# MIPI-toBTB-40-pin-AMOLED-HAT.net
KiCad netlist of a schematic drawn in EasyEDA Pro
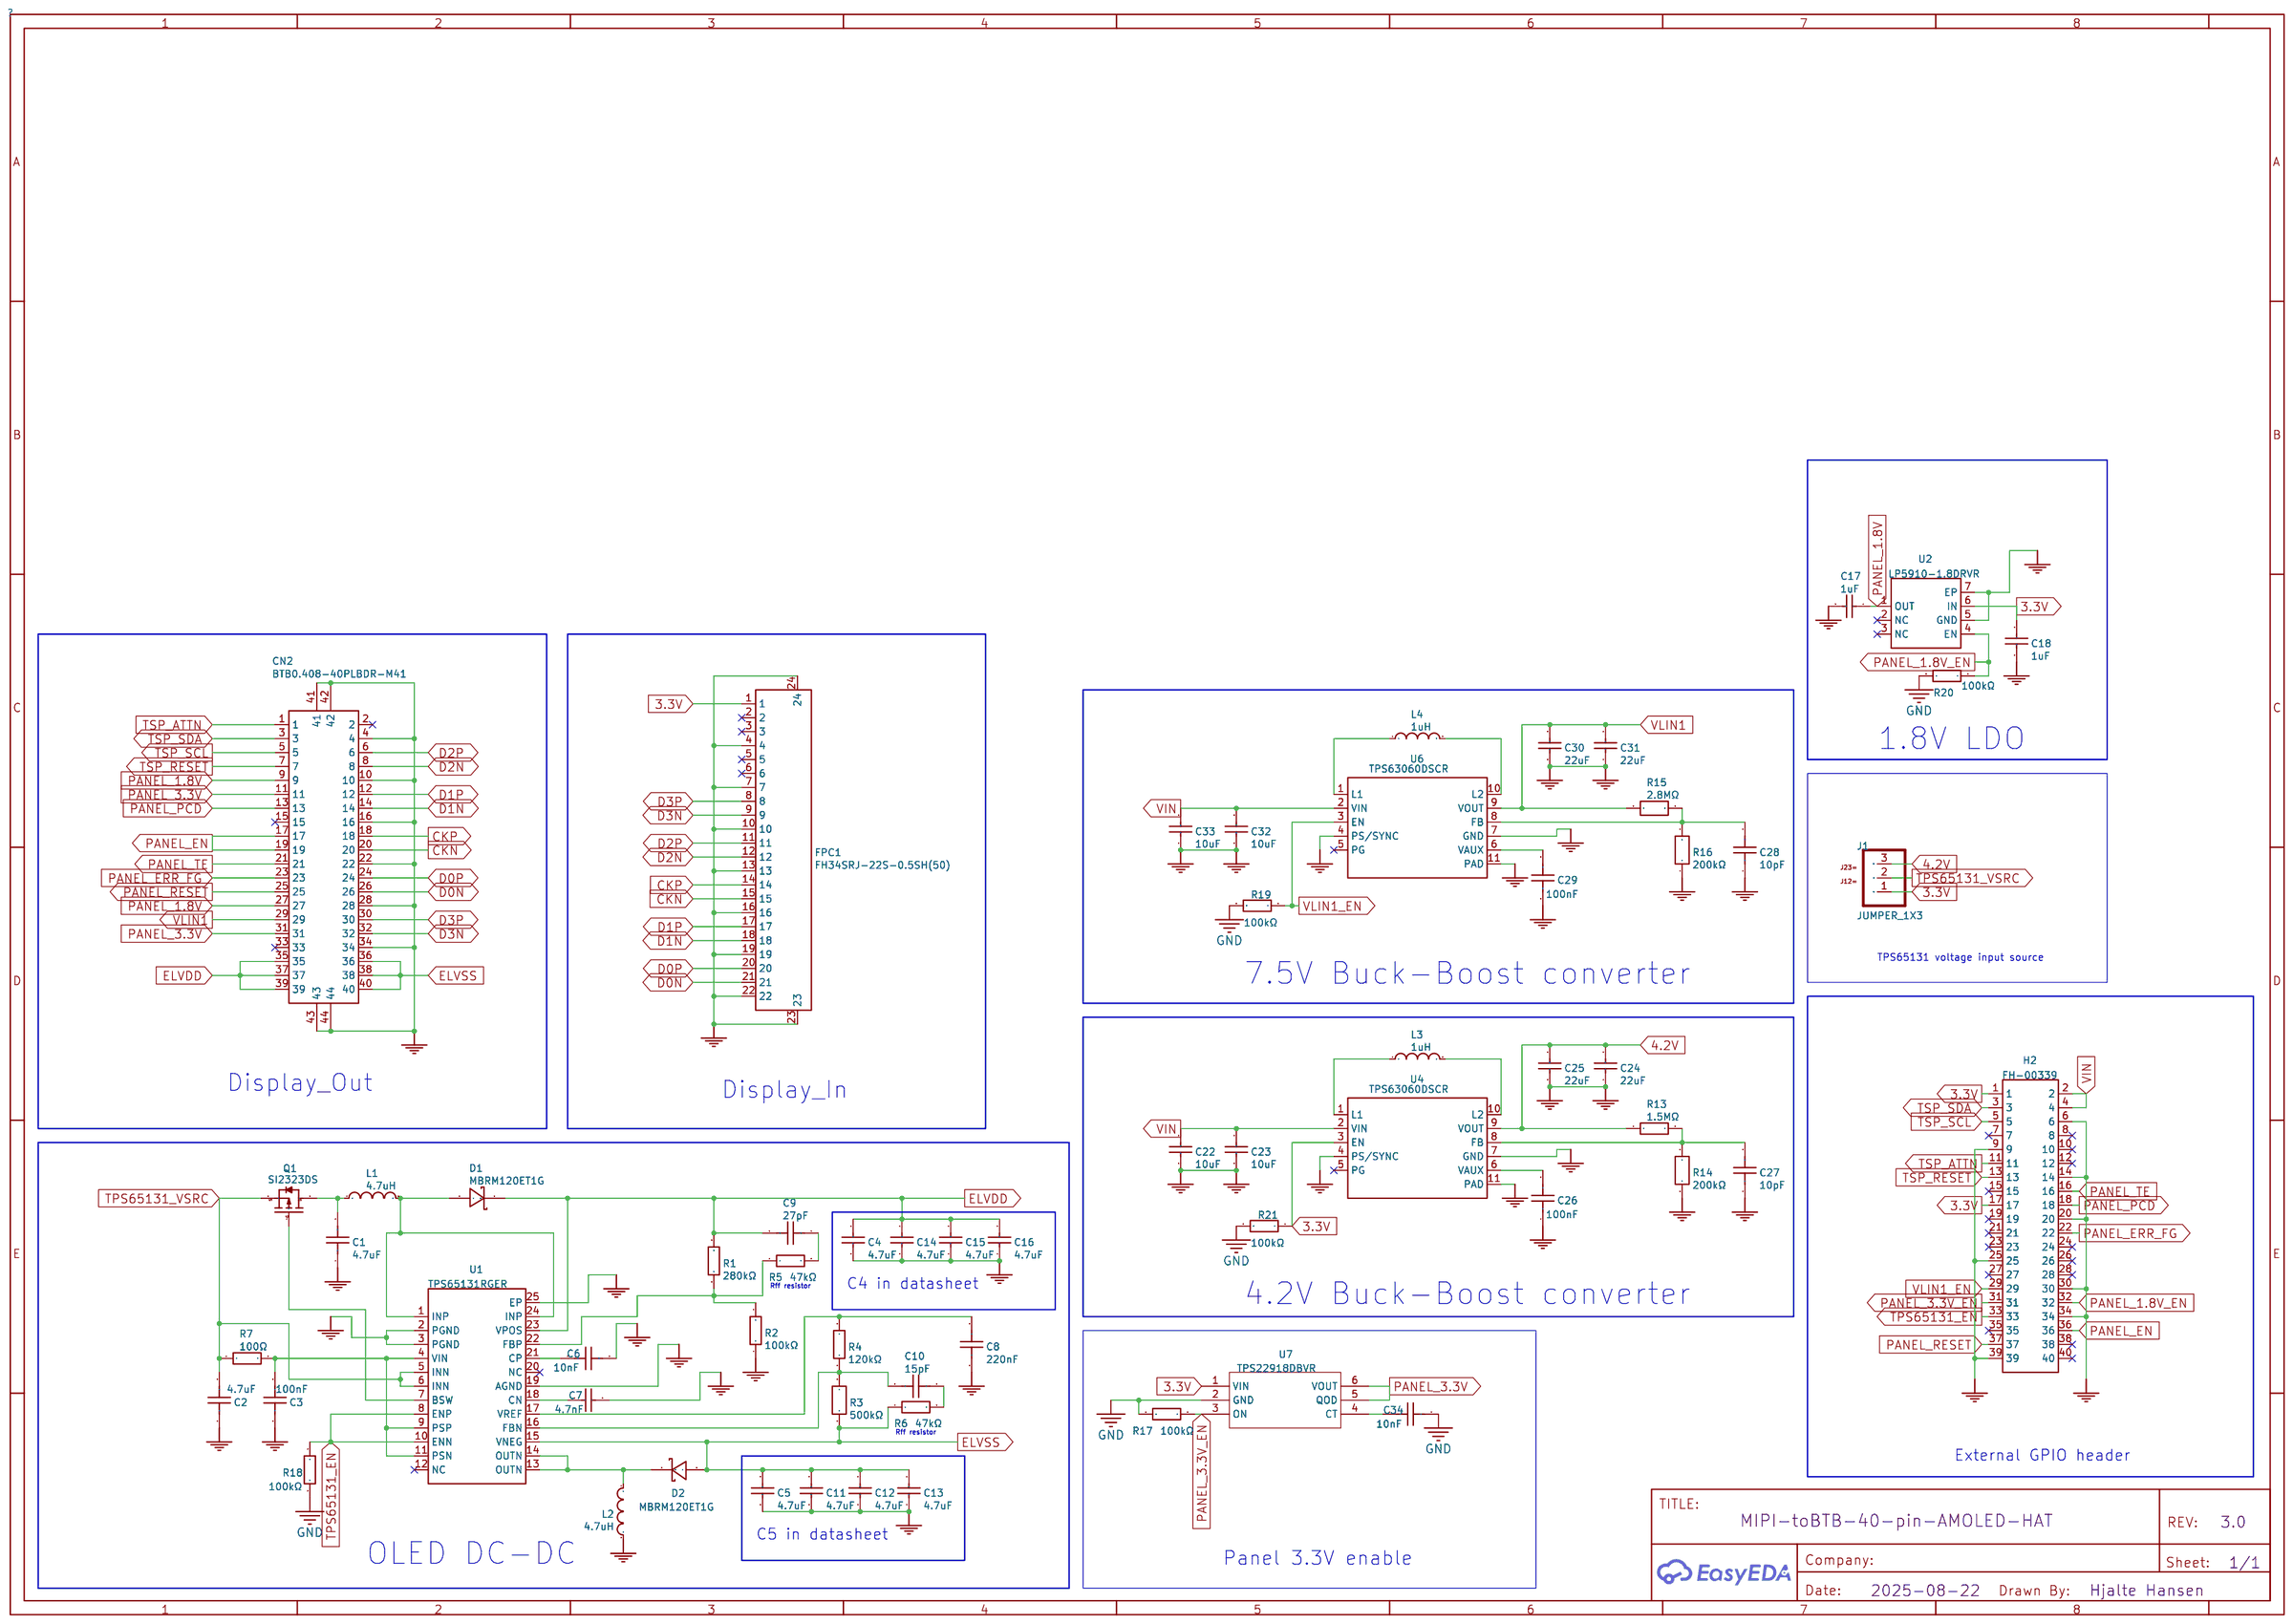
[diagram p0: schematic sheet]

(export (version "E")
  (design (tool "Eeschema 10.0.6"))
  (components
    (comp (ref "C1")
      (value "4.7uF")
      (footprint "easyedapro:C0402")
      (fields
        (field (name "Manufacturer Part") "CL05A475MQ5NRNC")
        (field (name "Manufacturer") "SAMSUNG(三星)")
        (field (name "Contributor") "LCSC")
      )
      (libsource (lib "") (part "4.7uF_1"))
    )
    (comp (ref "C2")
      (value "4.7uF")
      (footprint "easyedapro:C0402")
      (fields
        (field (name "Manufacturer Part") "CL05A475MQ5NRNC")
        (field (name "Manufacturer") "SAMSUNG(三星)")
        (field (name "Contributor") "LCSC")
      )
      (libsource (lib "") (part "4.7uF_1"))
    )
    (comp (ref "C3")
      (value "100nF")
      (footprint "easyedapro:C0402")
      (fields
        (field (name "Manufacturer Part") "CL05B104KP5NNNC")
        (field (name "Manufacturer") "SAMSUNG(三星)")
        (field (name "Contributor") "LCSC")
      )
      (libsource (lib "easyedapro") (part "100nF"))
    )
    (comp (ref "C4")
      (value "4.7uF")
      (footprint "easyedapro:C0805")
      (fields
        (field (name "Manufacturer Part") "CL21A475KAQNNNE")
        (field (name "Manufacturer") "SAMSUNG(三星)")
      )
      (libsource (lib "easyedapro") (part "4.7uF"))
    )
    (comp (ref "C5")
      (value "4.7uF")
      (footprint "easyedapro:C0805")
      (fields
        (field (name "Manufacturer Part") "CL21A475KAQNNNE")
        (field (name "Manufacturer") "SAMSUNG(三星)")
      )
      (libsource (lib "easyedapro") (part "4.7uF"))
    )
    (comp (ref "C6")
      (value "10nF")
      (footprint "easyedapro:C0402")
      (fields
        (field (name "Manufacturer Part") "CL05B103KO5NNNC")
        (field (name "Manufacturer") "SAMSUNG(三星)")
        (field (name "Contributor") "LCSC")
      )
      (libsource (lib "easyedapro") (part "10nF"))
    )
    (comp (ref "C7")
      (value "4.7nF")
      (footprint "easyedapro:C0603")
      (fields
        (field (name "Manufacturer Part") "CL10B472KB8NNNC")
        (field (name "Manufacturer") "SAMSUNG(三星)")
      )
      (libsource (lib "easyedapro") (part "4.7nF"))
    )
    (comp (ref "C8")
      (value "220nF")
      (footprint "easyedapro:C0402")
      (fields
        (field (name "Manufacturer Part") "CL05A224KQ5NNNC")
        (field (name "Manufacturer") "SAMSUNG(三星)")
        (field (name "Contributor") "LCSC")
      )
      (libsource (lib "easyedapro") (part "220nF"))
    )
    (comp (ref "C9")
      (value "27pF")
      (footprint "easyedapro:C0603")
      (fields
        (field (name "Manufacturer Part") "CC0603JRNPO7BN270")
        (field (name "Manufacturer") "YAGEO(国巨)")
        (field (name "Contributor") "lcsc")
      )
      (libsource (lib "easyedapro") (part "27pF"))
    )
    (comp (ref "C10")
      (value "15pF")
      (footprint "easyedapro:C0402")
      (fields
        (field (name "Manufacturer Part") "CC0402KRNPO7BN150")
        (field (name "Manufacturer") "YAGEO(国巨)")
        (field (name "Contributor") "lcsc")
      )
      (libsource (lib "easyedapro") (part "15pF"))
    )
    (comp (ref "C11")
      (value "4.7uF")
      (footprint "easyedapro:C0805")
      (fields
        (field (name "Manufacturer Part") "CL21A475KAQNNNE")
        (field (name "Manufacturer") "SAMSUNG(三星)")
      )
      (libsource (lib "easyedapro") (part "4.7uF"))
    )
    (comp (ref "C12")
      (value "4.7uF")
      (footprint "easyedapro:C0805")
      (fields
        (field (name "Manufacturer Part") "CL21A475KAQNNNE")
        (field (name "Manufacturer") "SAMSUNG(三星)")
      )
      (libsource (lib "easyedapro") (part "4.7uF"))
    )
    (comp (ref "C13")
      (value "4.7uF")
      (footprint "easyedapro:C0805")
      (fields
        (field (name "Manufacturer Part") "CL21A475KAQNNNE")
        (field (name "Manufacturer") "SAMSUNG(三星)")
      )
      (libsource (lib "easyedapro") (part "4.7uF"))
    )
    (comp (ref "C14")
      (value "4.7uF")
      (footprint "easyedapro:C0805")
      (fields
        (field (name "Manufacturer Part") "CL21A475KAQNNNE")
        (field (name "Manufacturer") "SAMSUNG(三星)")
      )
      (libsource (lib "easyedapro") (part "4.7uF"))
    )
    (comp (ref "C15")
      (value "4.7uF")
      (footprint "easyedapro:C0805")
      (fields
        (field (name "Manufacturer Part") "CL21A475KAQNNNE")
        (field (name "Manufacturer") "SAMSUNG(三星)")
      )
      (libsource (lib "easyedapro") (part "4.7uF"))
    )
    (comp (ref "C16")
      (value "4.7uF")
      (footprint "easyedapro:C0805")
      (fields
        (field (name "Manufacturer Part") "CL21A475KAQNNNE")
        (field (name "Manufacturer") "SAMSUNG(三星)")
      )
      (libsource (lib "easyedapro") (part "4.7uF"))
    )
    (comp (ref "C17")
      (value "1uF")
      (footprint "easyedapro:C0603")
      (fields
        (field (name "Manufacturer Part") "CL10A105KO8NNNC")
        (field (name "Manufacturer") "SAMSUNG(三星)")
      )
      (libsource (lib "easyedapro") (part "1uF"))
    )
    (comp (ref "C18")
      (value "1uF")
      (footprint "easyedapro:C0603")
      (fields
        (field (name "Manufacturer Part") "CL10A105KO8NNNC")
        (field (name "Manufacturer") "SAMSUNG(三星)")
      )
      (libsource (lib "") (part "1uF_1"))
    )
    (comp (ref "C22")
      (value "10uF")
      (footprint "easyedapro:C0805")
      (fields
        (field (name "Manufacturer Part") "CL21A106KOQNNNE")
        (field (name "Manufacturer") "SAMSUNG(三星)")
      )
      (libsource (lib "easyedapro") (part "10uF"))
    )
    (comp (ref "C23")
      (value "10uF")
      (footprint "easyedapro:C0805")
      (fields
        (field (name "Manufacturer Part") "CL21A106KOQNNNE")
        (field (name "Manufacturer") "SAMSUNG(三星)")
      )
      (libsource (lib "easyedapro") (part "10uF"))
    )
    (comp (ref "C24")
      (value "22uF")
      (footprint "easyedapro:C0805")
      (fields
        (field (name "Manufacturer Part") "CL21A226MOQNNNE")
        (field (name "Manufacturer") "SAMSUNG(三星)")
      )
      (libsource (lib "easyedapro") (part "22uF"))
    )
    (comp (ref "C25")
      (value "22uF")
      (footprint "easyedapro:C0805")
      (fields
        (field (name "Manufacturer Part") "CL21A226MOQNNNE")
        (field (name "Manufacturer") "SAMSUNG(三星)")
      )
      (libsource (lib "easyedapro") (part "22uF"))
    )
    (comp (ref "C26")
      (value "100nF")
      (footprint "easyedapro:C0402")
      (fields
        (field (name "Manufacturer Part") "CL05B104KP5NNNC")
        (field (name "Manufacturer") "SAMSUNG(三星)")
        (field (name "Contributor") "LCSC")
      )
      (libsource (lib "easyedapro") (part "100nF"))
    )
    (comp (ref "C27")
      (value "10pF")
      (footprint "easyedapro:C0402")
      (fields
        (field (name "Manufacturer Part") "CL05C100JB5NNNC")
        (field (name "Manufacturer") "SAMSUNG(三星)")
      )
      (libsource (lib "easyedapro") (part "10pF"))
    )
    (comp (ref "C28")
      (value "10pF")
      (footprint "easyedapro:C0402")
      (fields
        (field (name "Manufacturer Part") "CL05C100JB5NNNC")
        (field (name "Manufacturer") "SAMSUNG(三星)")
      )
      (libsource (lib "easyedapro") (part "10pF"))
    )
    (comp (ref "C29")
      (value "100nF")
      (footprint "easyedapro:C0402")
      (fields
        (field (name "Manufacturer Part") "CL05B104KP5NNNC")
        (field (name "Manufacturer") "SAMSUNG(三星)")
        (field (name "Contributor") "LCSC")
      )
      (libsource (lib "easyedapro") (part "100nF"))
    )
    (comp (ref "C30")
      (value "22uF")
      (footprint "easyedapro:C0805")
      (fields
        (field (name "Manufacturer Part") "CL21A226MOQNNNE")
        (field (name "Manufacturer") "SAMSUNG(三星)")
      )
      (libsource (lib "easyedapro") (part "22uF"))
    )
    (comp (ref "C31")
      (value "22uF")
      (footprint "easyedapro:C0805")
      (fields
        (field (name "Manufacturer Part") "CL21A226MOQNNNE")
        (field (name "Manufacturer") "SAMSUNG(三星)")
      )
      (libsource (lib "easyedapro") (part "22uF"))
    )
    (comp (ref "C32")
      (value "10uF")
      (footprint "easyedapro:C0805")
      (fields
        (field (name "Manufacturer Part") "CL21A106KOQNNNE")
        (field (name "Manufacturer") "SAMSUNG(三星)")
      )
      (libsource (lib "easyedapro") (part "10uF"))
    )
    (comp (ref "C33")
      (value "10uF")
      (footprint "easyedapro:C0805")
      (fields
        (field (name "Manufacturer Part") "CL21A106KOQNNNE")
        (field (name "Manufacturer") "SAMSUNG(三星)")
      )
      (libsource (lib "easyedapro") (part "10uF"))
    )
    (comp (ref "C34")
      (value "10nF")
      (footprint "easyedapro:C0402")
      (fields
        (field (name "Manufacturer Part") "CL05B103KO5NNNC")
        (field (name "Manufacturer") "SAMSUNG(三星)")
        (field (name "Contributor") "LCSC")
      )
      (libsource (lib "easyedapro") (part "10nF"))
    )
    (comp (ref "CN2")
      (value "BTB0.408-40PLBDR-M41")
      (footprint "easyedapro:CONN-SMD_40P-BTB0.408-40PLBDR-M41")
      (fields (field (name "Manufacturer") "XUNPU(讯普)") (field (name "Contributor") "lcsc"))
      (libsource (lib "easyedapro") (part "BTB0.408-40PLBDR-M41"))
    )
    (comp (ref "D1")
      (value "MBRM120ET1G")
      (footprint "easyedapro:POWERMITE_L2.0-W1.9-LS3.8-RD")
      (fields (field (name "Manufacturer") "onsemi(安森美)") (field (name "Contributor") "LCSC"))
      (libsource (lib "easyedapro") (part "MBRM120ET1G"))
    )
    (comp (ref "D2")
      (value "MBRM120ET1G")
      (footprint "easyedapro:POWERMITE_L2.0-W1.9-LS3.8-RD")
      (fields (field (name "Manufacturer") "onsemi(安森美)") (field (name "Contributor") "LCSC"))
      (libsource (lib "easyedapro") (part "MBRM120ET1G"))
    )
    (comp (ref "FPC1")
      (value "FH34SRJ-22S-0.5SH(50)")
      (footprint "easyedapro:FFC-SMD_22P-P0.50_HRS_FH34SRJ-22S-0.5SH")
      (fields (field (name "Manufacturer") "HRS(广濑)") (field (name "Contributor") "LCSC"))
      (libsource (lib "easyedapro") (part "FH34SRJ-22S-0.5SH(50)"))
    )
    (comp (ref "H2")
      (value "FH-00339")
      (footprint "easyedapro:HDR-SMD_40P-P2.54-V-F-R2-C20-S6.6_FH-00339")
      (fields (field (name "Manufacturer") "Liansheng(连盛)") (field (name "Contributor") "LCSC"))
      (libsource (lib "easyedapro") (part "FH-00339"))
    )
    (comp (ref "J1")
      (value "JUMPER_1X3")
      (footprint "easyedapro:JUMPER_SOLDER")
      (libsource (lib "easyedapro") (part "JUMPER_1X3"))
    )
    (comp (ref "L1")
      (value "4.7uH")
      (footprint "easyedapro:IND-SMD_L4.0-W4.0_FNR40XXS")
      (fields
        (field (name "Manufacturer Part") "FNR4020S4R7MT")
        (field (name "Manufacturer") "cjiang(长江微电)")
        (field (name "Contributor") "LCSC")
      )
      (libsource (lib "easyedapro") (part "4.7uH"))
    )
    (comp (ref "L2")
      (value "4.7uH")
      (footprint "easyedapro:IND-SMD_L4.0-W4.0_FNR40XXS")
      (fields
        (field (name "Manufacturer Part") "FNR4020S4R7MT")
        (field (name "Manufacturer") "cjiang(长江微电)")
        (field (name "Contributor") "LCSC")
      )
      (libsource (lib "") (part "4.7uH_1"))
    )
    (comp (ref "L3")
      (value "1uH")
      (footprint "easyedapro:IND-SMD_L4.5-W4.1_GSSM0420")
      (fields
        (field (name "Manufacturer Part") "MDA4020-1R0M")
        (field (name "Manufacturer") "KOHERelec(科或)")
        (field (name "Contributor") "lcsc")
      )
      (libsource (lib "easyedapro") (part "1uH"))
    )
    (comp (ref "L4")
      (value "1uH")
      (footprint "easyedapro:IND-SMD_L4.5-W4.1_GSSM0420")
      (fields
        (field (name "Manufacturer Part") "MDA4020-1R0M")
        (field (name "Manufacturer") "KOHERelec(科或)")
        (field (name "Contributor") "lcsc")
      )
      (libsource (lib "easyedapro") (part "1uH"))
    )
    (comp (ref "Q1")
      (value "SI2323DS")
      (footprint "easyedapro:SOT-23-3_L2.9-W1.3-P1.90-LS2.4-BR")
      (fields (field (name "Manufacturer") "TECH PUBLIC(台舟)") (field (name "Contributor") "lcsc"))
      (libsource (lib "easyedapro") (part "SI2323DS"))
    )
    (comp (ref "R1")
      (value "280kΩ")
      (footprint "easyedapro:R0603")
      (fields
        (field (name "Manufacturer Part") "0603WAF2803T5E")
        (field (name "Manufacturer") "UNI-ROYAL(厚声)")
      )
      (libsource (lib "easyedapro") (part "280kΩ"))
    )
    (comp (ref "R2")
      (value "100kΩ")
      (footprint "easyedapro:R0603")
      (fields
        (field (name "Manufacturer Part") "0603WAF1003T5E")
        (field (name "Manufacturer") "UNI-ROYAL(厚声)")
      )
      (libsource (lib "easyedapro") (part "100kΩ"))
    )
    (comp (ref "R3")
      (value "500kΩ")
      (footprint "easyedapro:R0603")
      (fields
        (field (name "Manufacturer Part") "AR03BTCX5003N")
        (field (name "Manufacturer") "Viking(光颉)")
        (field (name "Contributor") "LCSC")
      )
      (libsource (lib "easyedapro") (part "500kΩ"))
    )
    (comp (ref "R4")
      (value "120kΩ")
      (footprint "easyedapro:R0603")
      (fields
        (field (name "Manufacturer Part") "0603WAF1203T5E")
        (field (name "Manufacturer") "UNI-ROYAL(厚声)")
      )
      (libsource (lib "easyedapro") (part "120kΩ"))
    )
    (comp (ref "R5")
      (value "47kΩ")
      (footprint "easyedapro:R0603")
      (fields (field (name "Manufacturer Part") "RC0603FR-0747KL") (field (name "Manufacturer") "YAGEO(国巨)"))
      (libsource (lib "easyedapro") (part "47kΩ"))
    )
    (comp (ref "R6")
      (value "47kΩ")
      (footprint "easyedapro:R0603")
      (fields (field (name "Manufacturer Part") "RC0603FR-0747KL") (field (name "Manufacturer") "YAGEO(国巨)"))
      (libsource (lib "easyedapro") (part "47kΩ"))
    )
    (comp (ref "R7")
      (value "100Ω")
      (footprint "easyedapro:R0402")
      (fields (field (name "Manufacturer Part") "RC0402FR-07100RL") (field (name "Manufacturer") "YAGEO(国巨)"))
      (libsource (lib "easyedapro") (part "100Ω"))
    )
    (comp (ref "R13")
      (value "1.5MΩ")
      (footprint "easyedapro:R0603")
      (fields (field (name "Manufacturer Part") "RC0603FR-071M5L") (field (name "Manufacturer") "YAGEO(国巨)"))
      (libsource (lib "easyedapro") (part "1.5MΩ"))
    )
    (comp (ref "R14")
      (value "200kΩ")
      (footprint "easyedapro:R0805")
      (fields
        (field (name "Manufacturer Part") "FRC0805F2003TS")
        (field (name "Manufacturer") "FOJAN(富捷)")
        (field (name "Contributor") "lcsc")
      )
      (libsource (lib "easyedapro") (part "200kΩ"))
    )
    (comp (ref "R15")
      (value "2.8MΩ")
      (footprint "easyedapro:R0603")
      (fields
        (field (name "Manufacturer Part") "RC0603FR-072M8L")
        (field (name "Manufacturer") "YAGEO(国巨)")
        (field (name "Contributor") "LCSC")
      )
      (libsource (lib "easyedapro") (part "2.8MΩ"))
    )
    (comp (ref "R16")
      (value "200kΩ")
      (footprint "easyedapro:R0805")
      (fields
        (field (name "Manufacturer Part") "FRC0805F2003TS")
        (field (name "Manufacturer") "FOJAN(富捷)")
        (field (name "Contributor") "lcsc")
      )
      (libsource (lib "easyedapro") (part "200kΩ"))
    )
    (comp (ref "R17")
      (value "100kΩ")
      (footprint "easyedapro:R0603")
      (fields
        (field (name "Manufacturer Part") "0603WAF1003T5E")
        (field (name "Manufacturer") "UNI-ROYAL(厚声)")
      )
      (libsource (lib "easyedapro") (part "100kΩ"))
    )
    (comp (ref "R18")
      (value "100kΩ")
      (footprint "easyedapro:R0603")
      (fields
        (field (name "Manufacturer Part") "0603WAF1003T5E")
        (field (name "Manufacturer") "UNI-ROYAL(厚声)")
      )
      (libsource (lib "easyedapro") (part "100kΩ"))
    )
    (comp (ref "R19")
      (value "100kΩ")
      (footprint "easyedapro:R0603")
      (fields
        (field (name "Manufacturer Part") "0603WAF1003T5E")
        (field (name "Manufacturer") "UNI-ROYAL(厚声)")
      )
      (libsource (lib "easyedapro") (part "100kΩ"))
    )
    (comp (ref "R20")
      (value "100kΩ")
      (footprint "easyedapro:R0603")
      (fields
        (field (name "Manufacturer Part") "0603WAF1003T5E")
        (field (name "Manufacturer") "UNI-ROYAL(厚声)")
      )
      (libsource (lib "easyedapro") (part "100kΩ"))
    )
    (comp (ref "R21")
      (value "100kΩ")
      (footprint "easyedapro:R0603")
      (fields
        (field (name "Manufacturer Part") "0603WAF1003T5E")
        (field (name "Manufacturer") "UNI-ROYAL(厚声)")
      )
      (libsource (lib "easyedapro") (part "100kΩ"))
    )
    (comp (ref "U1")
      (value "TPS65131RGER")
      (footprint "easyedapro:QFN-24_L4.0-W4.0-P0.50-TL-EP2.6")
      (fields (field (name "Manufacturer") "TI(德州仪器)"))
      (libsource (lib "easyedapro") (part "TPS65131RGER"))
    )
    (comp (ref "U2")
      (value "LP5910-1.8DRVR")
      (footprint "easyedapro:WSON-6_L2.0-W2.0-P0.65-TL-EP")
      (fields (field (name "Manufacturer") "TI(德州仪器)") (field (name "Contributor") "LCSC"))
      (libsource (lib "easyedapro") (part "LP5910-1.8DRVR"))
    )
    (comp (ref "U4")
      (value "TPS63060DSCR")
      (footprint "easyedapro:WSON-10_L3.0-W3.0-P0.50-BL-EP-A")
      (fields (field (name "Manufacturer") "TI(德州仪器)"))
      (libsource (lib "easyedapro") (part "TPS63060DSCR"))
    )
    (comp (ref "U6")
      (value "TPS63060DSCR")
      (footprint "easyedapro:WSON-10_L3.0-W3.0-P0.50-BL-EP-A")
      (fields (field (name "Manufacturer") "TI(德州仪器)"))
      (libsource (lib "easyedapro") (part "TPS63060DSCR"))
    )
    (comp (ref "U7")
      (value "TPS22918DBVR")
      (footprint "easyedapro:SOT-23-6_L2.9-W1.6-P0.95-LS2.8-BR")
      (fields (field (name "Manufacturer") "TI(德州仪器)"))
      (libsource (lib "easyedapro") (part "TPS22918DBVR"))
    )
  )
  (nets
    (net (code "1") (name "3.3V") (class "Default")
      (node (ref "C18") (pin "1") (pinfunction "1_1") (pintype "input"))
      (node (ref "FPC1") (pin "1") (pinfunction "1_1") (pintype "unspecified"))
      (node (ref "H2") (pin "1") (pinfunction "1_1") (pintype "unspecified"))
      (node (ref "H2") (pin "17") (pinfunction "17_17") (pintype "unspecified"))
      (node (ref "J1") (pin "1") (pinfunction "VCC_1") (pintype "unspecified"))
      (node (ref "R21") (pin "1") (pinfunction "1_1") (pintype "input"))
      (node (ref "U2") (pin "6") (pinfunction "IN_6") (pintype "unspecified"))
      (node (ref "U4") (pin "3") (pinfunction "EN_3") (pintype "unspecified"))
      (node (ref "U7") (pin "1") (pinfunction "VIN_1") (pintype "unspecified"))
    )
    (net (code "2") (name "4.2V") (class "Default")
      (node (ref "C24") (pin "2") (pinfunction "2_2") (pintype "input"))
      (node (ref "C25") (pin "2") (pinfunction "2_2") (pintype "input"))
      (node (ref "J1") (pin "3") (pinfunction "GND_3") (pintype "unspecified"))
      (node (ref "R13") (pin "1") (pinfunction "1_1") (pintype "input"))
      (node (ref "U4") (pin "9") (pinfunction "VOUT_9") (pintype "unspecified"))
    )
    (net (code "3") (name "CKN") (class "Default")
      (node (ref "CN2") (pin "20") (pinfunction "20_20") (pintype "unspecified"))
      (node (ref "FPC1") (pin "15") (pinfunction "15_15") (pintype "unspecified"))
    )
    (net (code "4") (name "CKP") (class "Default")
      (node (ref "CN2") (pin "18") (pinfunction "18_18") (pintype "unspecified"))
      (node (ref "FPC1") (pin "14") (pinfunction "14_14") (pintype "unspecified"))
    )
    (net (code "5") (name "D0N") (class "Default")
      (node (ref "CN2") (pin "26") (pinfunction "26_26") (pintype "unspecified"))
      (node (ref "FPC1") (pin "21") (pinfunction "21_21") (pintype "unspecified"))
    )
    (net (code "6") (name "D0P") (class "Default")
      (node (ref "CN2") (pin "24") (pinfunction "24_24") (pintype "unspecified"))
      (node (ref "FPC1") (pin "20") (pinfunction "20_20") (pintype "unspecified"))
    )
    (net (code "7") (name "D1N") (class "Default")
      (node (ref "CN2") (pin "14") (pinfunction "14_14") (pintype "unspecified"))
      (node (ref "FPC1") (pin "18") (pinfunction "18_18") (pintype "unspecified"))
    )
    (net (code "8") (name "D1P") (class "Default")
      (node (ref "CN2") (pin "12") (pinfunction "12_12") (pintype "unspecified"))
      (node (ref "FPC1") (pin "17") (pinfunction "17_17") (pintype "unspecified"))
    )
    (net (code "9") (name "D2N") (class "Default")
      (node (ref "CN2") (pin "8") (pinfunction "8_8") (pintype "unspecified"))
      (node (ref "FPC1") (pin "12") (pinfunction "12_12") (pintype "unspecified"))
    )
    (net (code "10") (name "D2P") (class "Default")
      (node (ref "CN2") (pin "6") (pinfunction "6_6") (pintype "unspecified"))
      (node (ref "FPC1") (pin "11") (pinfunction "11_11") (pintype "unspecified"))
    )
    (net (code "11") (name "D3N") (class "Default")
      (node (ref "CN2") (pin "32") (pinfunction "32_32") (pintype "unspecified"))
      (node (ref "FPC1") (pin "9") (pinfunction "9_9") (pintype "unspecified"))
    )
    (net (code "12") (name "D3P") (class "Default")
      (node (ref "CN2") (pin "30") (pinfunction "30_30") (pintype "unspecified"))
      (node (ref "FPC1") (pin "8") (pinfunction "8_8") (pintype "unspecified"))
    )
    (net (code "13") (name "ELVDD") (class "Default")
      (node (ref "C14") (pin "2") (pinfunction "2_2") (pintype "input"))
      (node (ref "C15") (pin "2") (pinfunction "2_2") (pintype "input"))
      (node (ref "C16") (pin "2") (pinfunction "2_2") (pintype "input"))
      (node (ref "C4") (pin "2") (pinfunction "2_2") (pintype "input"))
      (node (ref "C9") (pin "2") (pinfunction "2_2") (pintype "unspecified"))
      (node (ref "CN2") (pin "35") (pinfunction "35_35") (pintype "unspecified"))
      (node (ref "CN2") (pin "37") (pinfunction "37_37") (pintype "unspecified"))
      (node (ref "CN2") (pin "39") (pinfunction "39_39") (pintype "unspecified"))
      (node (ref "D1") (pin "1") (pinfunction "C_1") (pintype "unspecified"))
      (node (ref "R1") (pin "2") (pinfunction "2_2") (pintype "input"))
      (node (ref "U1") (pin "23") (pinfunction "VPOS_23") (pintype "unspecified"))
    )
    (net (code "14") (name "ELVSS") (class "Default")
      (node (ref "C11") (pin "2") (pinfunction "2_2") (pintype "input"))
      (node (ref "C12") (pin "2") (pinfunction "2_2") (pintype "input"))
      (node (ref "C13") (pin "2") (pinfunction "2_2") (pintype "input"))
      (node (ref "C5") (pin "2") (pinfunction "2_2") (pintype "input"))
      (node (ref "CN2") (pin "36") (pinfunction "36_36") (pintype "unspecified"))
      (node (ref "CN2") (pin "38") (pinfunction "38_38") (pintype "unspecified"))
      (node (ref "CN2") (pin "40") (pinfunction "40_40") (pintype "unspecified"))
      (node (ref "D2") (pin "2") (pinfunction "A_2") (pintype "unspecified"))
      (node (ref "R3") (pin "1") (pinfunction "1_1") (pintype "unspecified"))
      (node (ref "R6") (pin "1") (pinfunction "1_1") (pintype "input"))
      (node (ref "U1") (pin "15") (pinfunction "VNEG_15") (pintype "unspecified"))
    )
    (net (code "15") (name "GND") (class "Default")
      (node (ref "C1") (pin "1") (pinfunction "1_1") (pintype "unspecified"))
      (node (ref "C11") (pin "1") (pinfunction "1_1") (pintype "input"))
      (node (ref "C12") (pin "1") (pinfunction "1_1") (pintype "input"))
      (node (ref "C13") (pin "1") (pinfunction "1_1") (pintype "input"))
      (node (ref "C14") (pin "1") (pinfunction "1_1") (pintype "input"))
      (node (ref "C15") (pin "1") (pinfunction "1_1") (pintype "input"))
      (node (ref "C16") (pin "1") (pinfunction "1_1") (pintype "input"))
      (node (ref "C17") (pin "2") (pinfunction "2_2") (pintype "input"))
      (node (ref "C18") (pin "2") (pinfunction "2_2") (pintype "input"))
      (node (ref "C2") (pin "1") (pinfunction "1_1") (pintype "unspecified"))
      (node (ref "C22") (pin "1") (pinfunction "1_1") (pintype "input"))
      (node (ref "C23") (pin "1") (pinfunction "1_1") (pintype "input"))
      (node (ref "C24") (pin "1") (pinfunction "1_1") (pintype "input"))
      (node (ref "C25") (pin "1") (pinfunction "1_1") (pintype "input"))
      (node (ref "C26") (pin "1") (pinfunction "1_1") (pintype "unspecified"))
      (node (ref "C27") (pin "1") (pinfunction "1_1") (pintype "unspecified"))
      (node (ref "C28") (pin "1") (pinfunction "1_1") (pintype "unspecified"))
      (node (ref "C29") (pin "1") (pinfunction "1_1") (pintype "unspecified"))
      (node (ref "C3") (pin "1") (pinfunction "1_1") (pintype "unspecified"))
      (node (ref "C30") (pin "1") (pinfunction "1_1") (pintype "input"))
      (node (ref "C31") (pin "1") (pinfunction "1_1") (pintype "input"))
      (node (ref "C32") (pin "1") (pinfunction "1_1") (pintype "input"))
      (node (ref "C33") (pin "1") (pinfunction "1_1") (pintype "input"))
      (node (ref "C34") (pin "2") (pinfunction "2_2") (pintype "unspecified"))
      (node (ref "C4") (pin "1") (pinfunction "1_1") (pintype "input"))
      (node (ref "C5") (pin "1") (pinfunction "1_1") (pintype "input"))
      (node (ref "C6") (pin "2") (pinfunction "2_2") (pintype "unspecified"))
      (node (ref "C7") (pin "2") (pinfunction "2_2") (pintype "input"))
      (node (ref "C8") (pin "1") (pinfunction "1_1") (pintype "unspecified"))
      (node (ref "CN2") (pin "10") (pinfunction "10_10") (pintype "unspecified"))
      (node (ref "CN2") (pin "16") (pinfunction "16_16") (pintype "unspecified"))
      (node (ref "CN2") (pin "22") (pinfunction "22_22") (pintype "unspecified"))
      (node (ref "CN2") (pin "28") (pinfunction "28_28") (pintype "unspecified"))
      (node (ref "CN2") (pin "34") (pinfunction "34_34") (pintype "unspecified"))
      (node (ref "CN2") (pin "4") (pinfunction "4_4") (pintype "unspecified"))
      (node (ref "CN2") (pin "41") (pinfunction "41_41") (pintype "unspecified"))
      (node (ref "CN2") (pin "42") (pinfunction "42_42") (pintype "unspecified"))
      (node (ref "CN2") (pin "43") (pinfunction "43_43") (pintype "unspecified"))
      (node (ref "CN2") (pin "44") (pinfunction "44_44") (pintype "unspecified"))
      (node (ref "FPC1") (pin "10") (pinfunction "10_10") (pintype "unspecified"))
      (node (ref "FPC1") (pin "13") (pinfunction "13_13") (pintype "unspecified"))
      (node (ref "FPC1") (pin "16") (pinfunction "16_16") (pintype "unspecified"))
      (node (ref "FPC1") (pin "19") (pinfunction "19_19") (pintype "unspecified"))
      (node (ref "FPC1") (pin "22") (pinfunction "22_22") (pintype "unspecified"))
      (node (ref "FPC1") (pin "23") (pinfunction "23_23") (pintype "unspecified"))
      (node (ref "FPC1") (pin "24") (pinfunction "24_24") (pintype "unspecified"))
      (node (ref "FPC1") (pin "4") (pinfunction "4_4") (pintype "unspecified"))
      (node (ref "FPC1") (pin "7") (pinfunction "7_7") (pintype "unspecified"))
      (node (ref "H2") (pin "14") (pinfunction "14_14") (pintype "unspecified"))
      (node (ref "H2") (pin "20") (pinfunction "20_20") (pintype "unspecified"))
      (node (ref "H2") (pin "25") (pinfunction "25_25") (pintype "unspecified"))
      (node (ref "H2") (pin "30") (pinfunction "30_30") (pintype "unspecified"))
      (node (ref "H2") (pin "34") (pinfunction "34_34") (pintype "unspecified"))
      (node (ref "H2") (pin "39") (pinfunction "39_39") (pintype "unspecified"))
      (node (ref "H2") (pin "6") (pinfunction "6_6") (pintype "unspecified"))
      (node (ref "H2") (pin "9") (pinfunction "9_9") (pintype "unspecified"))
      (node (ref "L2") (pin "2") (pinfunction "2_2") (pintype "unspecified"))
      (node (ref "R14") (pin "1") (pinfunction "1_1") (pintype "unspecified"))
      (node (ref "R16") (pin "1") (pinfunction "1_1") (pintype "unspecified"))
      (node (ref "R17") (pin "2") (pinfunction "2_2") (pintype "input"))
      (node (ref "R18") (pin "2") (pinfunction "2_2") (pintype "input"))
      (node (ref "R19") (pin "2") (pinfunction "2_2") (pintype "input"))
      (node (ref "R2") (pin "1") (pinfunction "1_1") (pintype "input"))
      (node (ref "R20") (pin "2") (pinfunction "2_2") (pintype "input"))
      (node (ref "R21") (pin "2") (pinfunction "2_2") (pintype "input"))
      (node (ref "U1") (pin "19") (pinfunction "AGND_19") (pintype "unspecified"))
      (node (ref "U1") (pin "2") (pinfunction "PGND_2") (pintype "unspecified"))
      (node (ref "U1") (pin "25") (pinfunction "EP_25") (pintype "unspecified"))
      (node (ref "U1") (pin "3") (pinfunction "PGND_3") (pintype "unspecified"))
      (node (ref "U2") (pin "5") (pinfunction "GND_5") (pintype "unspecified"))
      (node (ref "U2") (pin "7") (pinfunction "EP_7") (pintype "unspecified"))
      (node (ref "U4") (pin "11") (pinfunction "PAD_11") (pintype "unspecified"))
      (node (ref "U4") (pin "4") (pinfunction "PS/SYNC_4") (pintype "unspecified"))
      (node (ref "U4") (pin "7") (pinfunction "GND_7") (pintype "unspecified"))
      (node (ref "U6") (pin "11") (pinfunction "PAD_11") (pintype "unspecified"))
      (node (ref "U6") (pin "4") (pinfunction "PS/SYNC_4") (pintype "unspecified"))
      (node (ref "U6") (pin "7") (pinfunction "GND_7") (pintype "unspecified"))
      (node (ref "U7") (pin "2") (pinfunction "GND_2") (pintype "unspecified"))
    )
    (net (code "16") (name "Net-(C9-Pad1)") (class "Default")
      (node (ref "C9") (pin "1") (pinfunction "1_1") (pintype "unspecified"))
      (node (ref "R5") (pin "2") (pinfunction "2_2") (pintype "input"))
    )
    (net (code "17") (name "Net-(C10-Pad1)") (class "Default")
      (node (ref "C10") (pin "1") (pinfunction "1_1") (pintype "unspecified"))
      (node (ref "R6") (pin "2") (pinfunction "2_2") (pintype "input"))
    )
    (net (code "18") (name "Net-(D1-A)") (class "Default")
      (node (ref "D1") (pin "2") (pinfunction "A_2") (pintype "unspecified"))
      (node (ref "L1") (pin "2") (pinfunction "2_2") (pintype "unspecified"))
      (node (ref "U1") (pin "1") (pinfunction "INP_1") (pintype "unspecified"))
      (node (ref "U1") (pin "24") (pinfunction "INP_24") (pintype "unspecified"))
    )
    (net (code "19") (name "Net-(D2-C)") (class "Default")
      (node (ref "D2") (pin "1") (pinfunction "C_1") (pintype "unspecified"))
      (node (ref "L2") (pin "1") (pinfunction "1_1") (pintype "unspecified"))
      (node (ref "U1") (pin "13") (pinfunction "OUTN_13") (pintype "unspecified"))
      (node (ref "U1") (pin "14") (pinfunction "OUTN_14") (pintype "unspecified"))
    )
    (net (code "20") (name "Net-(Q1-D)") (class "Default")
      (node (ref "C1") (pin "2") (pinfunction "2_2") (pintype "unspecified"))
      (node (ref "L1") (pin "1") (pinfunction "1_1") (pintype "unspecified"))
      (node (ref "Q1") (pin "3") (pinfunction "D_3") (pintype "unspecified"))
    )
    (net (code "21") (name "Net-(Q1-G)") (class "Default")
      (node (ref "Q1") (pin "1") (pinfunction "G_1") (pintype "unspecified"))
      (node (ref "U1") (pin "7") (pinfunction "BSW_7") (pintype "unspecified"))
    )
    (net (code "22") (name "Net-(U1-CN)") (class "Default")
      (node (ref "C7") (pin "1") (pinfunction "1_1") (pintype "input"))
      (node (ref "U1") (pin "18") (pinfunction "CN_18") (pintype "unspecified"))
    )
    (net (code "23") (name "Net-(U1-CP)") (class "Default")
      (node (ref "C6") (pin "1") (pinfunction "1_1") (pintype "unspecified"))
      (node (ref "U1") (pin "21") (pinfunction "CP_21") (pintype "unspecified"))
    )
    (net (code "24") (name "Net-(U1-FBN)") (class "Default")
      (node (ref "C10") (pin "2") (pinfunction "2_2") (pintype "unspecified"))
      (node (ref "R3") (pin "2") (pinfunction "2_2") (pintype "unspecified"))
      (node (ref "R4") (pin "1") (pinfunction "1_1") (pintype "input"))
      (node (ref "U1") (pin "16") (pinfunction "FBN_16") (pintype "unspecified"))
    )
    (net (code "25") (name "Net-(U1-FBP)") (class "Default")
      (node (ref "R1") (pin "1") (pinfunction "1_1") (pintype "input"))
      (node (ref "R2") (pin "2") (pinfunction "2_2") (pintype "input"))
      (node (ref "R5") (pin "1") (pinfunction "1_1") (pintype "input"))
      (node (ref "U1") (pin "22") (pinfunction "FBP_22") (pintype "unspecified"))
    )
    (net (code "26") (name "Net-(U1-PSN)") (class "Default")
      (node (ref "C3") (pin "2") (pinfunction "2_2") (pintype "unspecified"))
      (node (ref "R7") (pin "2") (pinfunction "2_2") (pintype "input"))
      (node (ref "U1") (pin "11") (pinfunction "PSN_11") (pintype "unspecified"))
      (node (ref "U1") (pin "4") (pinfunction "VIN_4") (pintype "unspecified"))
      (node (ref "U1") (pin "9") (pinfunction "PSP_9") (pintype "unspecified"))
    )
    (net (code "27") (name "Net-(U1-VREF)") (class "Default")
      (node (ref "C8") (pin "2") (pinfunction "2_2") (pintype "unspecified"))
      (node (ref "R4") (pin "2") (pinfunction "2_2") (pintype "input"))
      (node (ref "U1") (pin "17") (pinfunction "VREF_17") (pintype "unspecified"))
    )
    (net (code "28") (name "Net-(U4-FB)") (class "Default")
      (node (ref "C27") (pin "2") (pinfunction "2_2") (pintype "unspecified"))
      (node (ref "R13") (pin "2") (pinfunction "2_2") (pintype "input"))
      (node (ref "R14") (pin "2") (pinfunction "2_2") (pintype "unspecified"))
      (node (ref "U4") (pin "8") (pinfunction "FB_8") (pintype "unspecified"))
    )
    (net (code "29") (name "Net-(U4-L1)") (class "Default")
      (node (ref "L3") (pin "1") (pinfunction "1_1") (pintype "unspecified"))
      (node (ref "U4") (pin "1") (pinfunction "L1_1") (pintype "unspecified"))
    )
    (net (code "30") (name "Net-(U4-L2)") (class "Default")
      (node (ref "L3") (pin "2") (pinfunction "2_2") (pintype "unspecified"))
      (node (ref "U4") (pin "10") (pinfunction "L2_10") (pintype "unspecified"))
    )
    (net (code "31") (name "Net-(U4-VAUX)") (class "Default")
      (node (ref "C26") (pin "2") (pinfunction "2_2") (pintype "unspecified"))
      (node (ref "U4") (pin "6") (pinfunction "VAUX_6") (pintype "unspecified"))
    )
    (net (code "32") (name "Net-(U6-FB)") (class "Default")
      (node (ref "C28") (pin "2") (pinfunction "2_2") (pintype "unspecified"))
      (node (ref "R15") (pin "2") (pinfunction "2_2") (pintype "unspecified"))
      (node (ref "R16") (pin "2") (pinfunction "2_2") (pintype "unspecified"))
      (node (ref "U6") (pin "8") (pinfunction "FB_8") (pintype "unspecified"))
    )
    (net (code "33") (name "Net-(U6-L1)") (class "Default")
      (node (ref "L4") (pin "1") (pinfunction "1_1") (pintype "unspecified"))
      (node (ref "U6") (pin "1") (pinfunction "L1_1") (pintype "unspecified"))
    )
    (net (code "34") (name "Net-(U6-L2)") (class "Default")
      (node (ref "L4") (pin "2") (pinfunction "2_2") (pintype "unspecified"))
      (node (ref "U6") (pin "10") (pinfunction "L2_10") (pintype "unspecified"))
    )
    (net (code "35") (name "Net-(U6-VAUX)") (class "Default")
      (node (ref "C29") (pin "2") (pinfunction "2_2") (pintype "unspecified"))
      (node (ref "U6") (pin "6") (pinfunction "VAUX_6") (pintype "unspecified"))
    )
    (net (code "36") (name "Net-(U7-CT)") (class "Default")
      (node (ref "C34") (pin "1") (pinfunction "1_1") (pintype "unspecified"))
      (node (ref "U7") (pin "4") (pinfunction "CT_4") (pintype "unspecified"))
    )
    (net (code "37") (name "PANEL_1.8V") (class "Default")
      (node (ref "C17") (pin "1") (pinfunction "1_1") (pintype "input"))
      (node (ref "CN2") (pin "27") (pinfunction "27_27") (pintype "unspecified"))
      (node (ref "CN2") (pin "9") (pinfunction "9_9") (pintype "unspecified"))
      (node (ref "U2") (pin "1") (pinfunction "OUT_1") (pintype "unspecified"))
    )
    (net (code "38") (name "PANEL_1.8V_EN") (class "Default")
      (node (ref "H2") (pin "32") (pinfunction "32_32") (pintype "unspecified"))
      (node (ref "R20") (pin "1") (pinfunction "1_1") (pintype "input"))
      (node (ref "U2") (pin "4") (pinfunction "EN_4") (pintype "unspecified"))
    )
    (net (code "39") (name "PANEL_3.3V") (class "Default")
      (node (ref "CN2") (pin "11") (pinfunction "11_11") (pintype "unspecified"))
      (node (ref "CN2") (pin "31") (pinfunction "31_31") (pintype "unspecified"))
      (node (ref "U7") (pin "5") (pinfunction "QOD_5") (pintype "unspecified"))
      (node (ref "U7") (pin "6") (pinfunction "VOUT_6") (pintype "unspecified"))
    )
    (net (code "40") (name "PANEL_3.3V_EN") (class "Default")
      (node (ref "H2") (pin "31") (pinfunction "31_31") (pintype "unspecified"))
      (node (ref "R17") (pin "1") (pinfunction "1_1") (pintype "input"))
      (node (ref "U7") (pin "3") (pinfunction "ON_3") (pintype "unspecified"))
    )
    (net (code "41") (name "PANEL_EN") (class "Default")
      (node (ref "CN2") (pin "17") (pinfunction "17_17") (pintype "unspecified"))
      (node (ref "CN2") (pin "19") (pinfunction "19_19") (pintype "unspecified"))
      (node (ref "H2") (pin "36") (pinfunction "36_36") (pintype "unspecified"))
    )
    (net (code "42") (name "PANEL_ERR_FG") (class "Default")
      (node (ref "CN2") (pin "23") (pinfunction "23_23") (pintype "unspecified"))
      (node (ref "H2") (pin "22") (pinfunction "22_22") (pintype "unspecified"))
    )
    (net (code "43") (name "PANEL_PCD") (class "Default")
      (node (ref "CN2") (pin "13") (pinfunction "13_13") (pintype "unspecified"))
      (node (ref "H2") (pin "18") (pinfunction "18_18") (pintype "unspecified"))
    )
    (net (code "44") (name "PANEL_RESET") (class "Default")
      (node (ref "CN2") (pin "25") (pinfunction "25_25") (pintype "unspecified"))
      (node (ref "H2") (pin "37") (pinfunction "37_37") (pintype "unspecified"))
    )
    (net (code "45") (name "PANEL_TE") (class "Default")
      (node (ref "CN2") (pin "21") (pinfunction "21_21") (pintype "unspecified"))
      (node (ref "H2") (pin "16") (pinfunction "16_16") (pintype "unspecified"))
    )
    (net (code "46") (name "TPS65131_EN") (class "Default")
      (node (ref "H2") (pin "33") (pinfunction "33_33") (pintype "unspecified"))
      (node (ref "R18") (pin "1") (pinfunction "1_1") (pintype "input"))
      (node (ref "U1") (pin "10") (pinfunction "ENN_10") (pintype "unspecified"))
      (node (ref "U1") (pin "8") (pinfunction "ENP_8") (pintype "unspecified"))
    )
    (net (code "47") (name "TPS65131_VSRC") (class "Default")
      (node (ref "C2") (pin "2") (pinfunction "2_2") (pintype "unspecified"))
      (node (ref "J1") (pin "2") (pinfunction "I/O_2") (pintype "unspecified"))
      (node (ref "Q1") (pin "2") (pinfunction "S_2") (pintype "unspecified"))
      (node (ref "R7") (pin "1") (pinfunction "1_1") (pintype "input"))
      (node (ref "U1") (pin "5") (pinfunction "INN_5") (pintype "unspecified"))
      (node (ref "U1") (pin "6") (pinfunction "INN_6") (pintype "unspecified"))
    )
    (net (code "48") (name "TSP_ATTN") (class "Default")
      (node (ref "CN2") (pin "1") (pinfunction "1_1") (pintype "unspecified"))
      (node (ref "H2") (pin "11") (pinfunction "11_11") (pintype "unspecified"))
    )
    (net (code "49") (name "TSP_RESET") (class "Default")
      (node (ref "CN2") (pin "7") (pinfunction "7_7") (pintype "unspecified"))
      (node (ref "H2") (pin "13") (pinfunction "13_13") (pintype "unspecified"))
    )
    (net (code "50") (name "TSP_SCL") (class "Default")
      (node (ref "CN2") (pin "5") (pinfunction "5_5") (pintype "unspecified"))
      (node (ref "H2") (pin "5") (pinfunction "5_5") (pintype "unspecified"))
    )
    (net (code "51") (name "TSP_SDA") (class "Default")
      (node (ref "CN2") (pin "3") (pinfunction "3_3") (pintype "unspecified"))
      (node (ref "H2") (pin "3") (pinfunction "3_3") (pintype "unspecified"))
    )
    (net (code "52") (name "VIN") (class "Default")
      (node (ref "C22") (pin "2") (pinfunction "2_2") (pintype "input"))
      (node (ref "C23") (pin "2") (pinfunction "2_2") (pintype "input"))
      (node (ref "C32") (pin "2") (pinfunction "2_2") (pintype "input"))
      (node (ref "C33") (pin "2") (pinfunction "2_2") (pintype "input"))
      (node (ref "H2") (pin "2") (pinfunction "2_2") (pintype "unspecified"))
      (node (ref "H2") (pin "4") (pinfunction "4_4") (pintype "unspecified"))
      (node (ref "U4") (pin "2") (pinfunction "VIN_2") (pintype "unspecified"))
      (node (ref "U6") (pin "2") (pinfunction "VIN_2") (pintype "unspecified"))
    )
    (net (code "53") (name "VLIN1") (class "Default")
      (node (ref "C30") (pin "2") (pinfunction "2_2") (pintype "input"))
      (node (ref "C31") (pin "2") (pinfunction "2_2") (pintype "input"))
      (node (ref "CN2") (pin "29") (pinfunction "29_29") (pintype "unspecified"))
      (node (ref "R15") (pin "1") (pinfunction "1_1") (pintype "unspecified"))
      (node (ref "U6") (pin "9") (pinfunction "VOUT_9") (pintype "unspecified"))
    )
    (net (code "54") (name "VLIN1_EN") (class "Default")
      (node (ref "H2") (pin "29") (pinfunction "29_29") (pintype "unspecified"))
      (node (ref "R19") (pin "1") (pinfunction "1_1") (pintype "input"))
      (node (ref "U6") (pin "3") (pinfunction "EN_3") (pintype "unspecified"))
    )
    (net (code "55") (name "unconnected-(CN2-Pad2)") (class "Default")
      (node (ref "CN2") (pin "2") (pinfunction "2_2") (pintype "unspecified+no_connect"))
    )
    (net (code "56") (name "unconnected-(CN2-Pad15)") (class "Default")
      (node (ref "CN2") (pin "15") (pinfunction "15_15") (pintype "unspecified+no_connect"))
    )
    (net (code "57") (name "unconnected-(CN2-Pad33)") (class "Default")
      (node (ref "CN2") (pin "33") (pinfunction "33_33") (pintype "unspecified+no_connect"))
    )
    (net (code "58") (name "unconnected-(FPC1-Pad2)") (class "Default")
      (node (ref "FPC1") (pin "2") (pinfunction "2_2") (pintype "unspecified+no_connect"))
    )
    (net (code "59") (name "unconnected-(FPC1-Pad3)") (class "Default")
      (node (ref "FPC1") (pin "3") (pinfunction "3_3") (pintype "unspecified+no_connect"))
    )
    (net (code "60") (name "unconnected-(FPC1-Pad5)") (class "Default")
      (node (ref "FPC1") (pin "5") (pinfunction "5_5") (pintype "unspecified+no_connect"))
    )
    (net (code "61") (name "unconnected-(FPC1-Pad6)") (class "Default")
      (node (ref "FPC1") (pin "6") (pinfunction "6_6") (pintype "unspecified+no_connect"))
    )
    (net (code "62") (name "unconnected-(H2-Pad7)") (class "Default")
      (node (ref "H2") (pin "7") (pinfunction "7_7") (pintype "unspecified+no_connect"))
    )
    (net (code "63") (name "unconnected-(H2-Pad8)") (class "Default")
      (node (ref "H2") (pin "8") (pinfunction "8_8") (pintype "unspecified+no_connect"))
    )
    (net (code "64") (name "unconnected-(H2-Pad10)") (class "Default")
      (node (ref "H2") (pin "10") (pinfunction "10_10") (pintype "unspecified+no_connect"))
    )
    (net (code "65") (name "unconnected-(H2-Pad12)") (class "Default")
      (node (ref "H2") (pin "12") (pinfunction "12_12") (pintype "unspecified+no_connect"))
    )
    (net (code "66") (name "unconnected-(H2-Pad15)") (class "Default")
      (node (ref "H2") (pin "15") (pinfunction "15_15") (pintype "unspecified+no_connect"))
    )
    (net (code "67") (name "unconnected-(H2-Pad19)") (class "Default")
      (node (ref "H2") (pin "19") (pinfunction "19_19") (pintype "unspecified+no_connect"))
    )
    (net (code "68") (name "unconnected-(H2-Pad21)") (class "Default")
      (node (ref "H2") (pin "21") (pinfunction "21_21") (pintype "unspecified+no_connect"))
    )
    (net (code "69") (name "unconnected-(H2-Pad23)") (class "Default")
      (node (ref "H2") (pin "23") (pinfunction "23_23") (pintype "unspecified+no_connect"))
    )
    (net (code "70") (name "unconnected-(H2-Pad24)") (class "Default")
      (node (ref "H2") (pin "24") (pinfunction "24_24") (pintype "unspecified+no_connect"))
    )
    (net (code "71") (name "unconnected-(H2-Pad26)") (class "Default")
      (node (ref "H2") (pin "26") (pinfunction "26_26") (pintype "unspecified+no_connect"))
    )
    (net (code "72") (name "unconnected-(H2-Pad27)") (class "Default")
      (node (ref "H2") (pin "27") (pinfunction "27_27") (pintype "unspecified+no_connect"))
    )
    (net (code "73") (name "unconnected-(H2-Pad28)") (class "Default")
      (node (ref "H2") (pin "28") (pinfunction "28_28") (pintype "unspecified+no_connect"))
    )
    (net (code "74") (name "unconnected-(H2-Pad35)") (class "Default")
      (node (ref "H2") (pin "35") (pinfunction "35_35") (pintype "unspecified+no_connect"))
    )
    (net (code "75") (name "unconnected-(H2-Pad38)") (class "Default")
      (node (ref "H2") (pin "38") (pinfunction "38_38") (pintype "unspecified+no_connect"))
    )
    (net (code "76") (name "unconnected-(H2-Pad40)") (class "Default")
      (node (ref "H2") (pin "40") (pinfunction "40_40") (pintype "unspecified+no_connect"))
    )
    (net (code "77") (name "unconnected-(U1-NC-Pad12)") (class "Default")
      (node (ref "U1") (pin "12") (pinfunction "NC_12") (pintype "unspecified+no_connect"))
    )
    (net (code "78") (name "unconnected-(U1-NC-Pad20)") (class "Default")
      (node (ref "U1") (pin "20") (pinfunction "NC_20") (pintype "unspecified+no_connect"))
    )
    (net (code "79") (name "unconnected-(U2-NC-Pad2)") (class "Default")
      (node (ref "U2") (pin "2") (pinfunction "NC_2") (pintype "unspecified+no_connect"))
    )
    (net (code "80") (name "unconnected-(U2-NC-Pad3)") (class "Default")
      (node (ref "U2") (pin "3") (pinfunction "NC_3") (pintype "unspecified+no_connect"))
    )
    (net (code "81") (name "unconnected-(U4-PG-Pad5)") (class "Default")
      (node (ref "U4") (pin "5") (pinfunction "PG_5") (pintype "unspecified+no_connect"))
    )
    (net (code "82") (name "unconnected-(U6-PG-Pad5)") (class "Default")
      (node (ref "U6") (pin "5") (pinfunction "PG_5") (pintype "unspecified+no_connect"))
    )
  )
)
